# heater.net
KiCad netlist of a schematic drawn in EAGLE
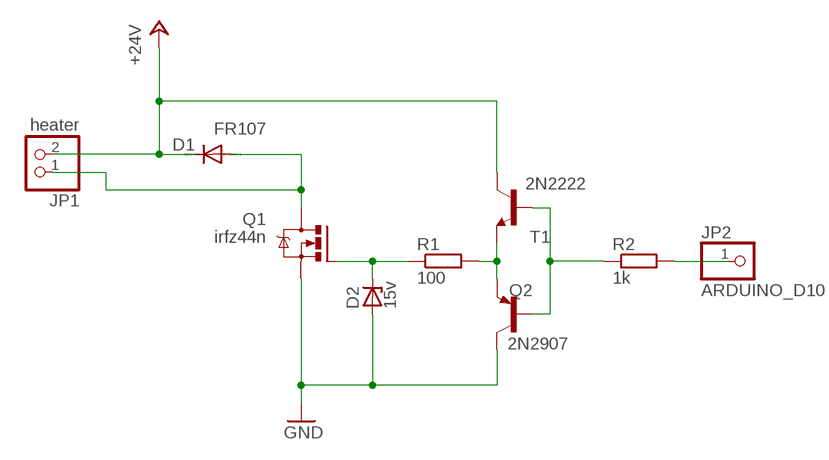
[diagram p0: schematic, sheet 1]

(export (version "E")
  (design (tool "Eeschema 10.0.6"))
  (components
    (comp (ref "D1")
      (value "FR107")
      (footprint "eagle-import:DO41-10")
      (libsource (lib "eagle-import") (part "1N4004"))
    )
    (comp (ref "D2")
      (value "15v")
      (footprint "eagle-import:DO34Z7")
      (libsource (lib "eagle-import") (part "ZENER-DIODEDO34-7"))
    )
    (comp (ref "JP1")
      (value "heater")
      (footprint "eagle-import:1X02")
      (libsource (lib "eagle-import") (part "PINHD-1X2"))
    )
    (comp (ref "JP2")
      (value "ARDUINO_D10")
      (footprint "eagle-import:1X01")
      (libsource (lib "eagle-import") (part "PINHD-1X1"))
    )
    (comp (ref "Q1")
      (value "irfz44n")
      (footprint "eagle-import:TO220BH")
      (libsource (lib "eagle-import") (part "IRLZ44Z"))
    )
    (comp (ref "Q2")
      (value "2N2907")
      (footprint "eagle-import:TO5")
      (libsource (lib "eagle-import") (part "2N2905"))
    )
    (comp (ref "R1")
      (value "100")
      (footprint "eagle-import:0204_5")
      (libsource (lib "eagle-import") (part "R-EU_0204/5"))
    )
    (comp (ref "R2")
      (value "1k")
      (footprint "eagle-import:0204_5")
      (libsource (lib "eagle-import") (part "R-EU_0204/5"))
    )
    (comp (ref "T1")
      (value "2N2222")
      (footprint "eagle-import:TO18")
      (libsource (lib "eagle-import") (part "2N2222"))
    )
  )
  (nets
    (net (code "1") (name "+24V") (class "Default")
      (node (ref "D1") (pin "C") (pinfunction "C_C") (pintype "passive"))
      (node (ref "JP1") (pin "2") (pinfunction "2_2") (pintype "passive"))
      (node (ref "T1") (pin "3") (pinfunction "C_3") (pintype "passive"))
    )
    (net (code "2") (name "GND") (class "Default")
      (node (ref "D2") (pin "A") (pinfunction "A_A") (pintype "passive"))
      (node (ref "Q1") (pin "S") (pinfunction "S_S") (pintype "passive"))
      (node (ref "Q2") (pin "3") (pinfunction "C_3") (pintype "passive"))
    )
    (net (code "3") (name "Net-(D1-PadA)") (class "Default")
      (node (ref "D1") (pin "A") (pinfunction "A_A") (pintype "passive"))
      (node (ref "JP1") (pin "1") (pinfunction "1_1") (pintype "passive"))
      (node (ref "Q1") (pin "D") (pinfunction "D_D") (pintype "passive"))
    )
    (net (code "4") (name "Net-(D2-PadC)") (class "Default")
      (node (ref "D2") (pin "C") (pinfunction "C_C") (pintype "passive"))
      (node (ref "Q1") (pin "G") (pinfunction "G_G") (pintype "passive"))
      (node (ref "R1") (pin "1") (pinfunction "1_1") (pintype "passive"))
    )
    (net (code "5") (name "Net-(JP2-Pad1)") (class "Default")
      (node (ref "JP2") (pin "1") (pinfunction "1_1") (pintype "passive"))
      (node (ref "R2") (pin "2") (pinfunction "2_2") (pintype "passive"))
    )
    (net (code "6") (name "Net-(Q2-B)") (class "Default")
      (node (ref "Q2") (pin "2") (pinfunction "B_2") (pintype "passive"))
      (node (ref "R2") (pin "1") (pinfunction "1_1") (pintype "passive"))
      (node (ref "T1") (pin "2") (pinfunction "B_2") (pintype "passive"))
    )
    (net (code "7") (name "Net-(Q2-E)") (class "Default")
      (node (ref "Q2") (pin "1") (pinfunction "E_1") (pintype "passive"))
      (node (ref "R1") (pin "2") (pinfunction "2_2") (pintype "passive"))
      (node (ref "T1") (pin "1") (pinfunction "E_1") (pintype "passive"))
    )
  )
)
